# environmental_monitor.net
KiCad netlist of a schematic drawn in EAGLE
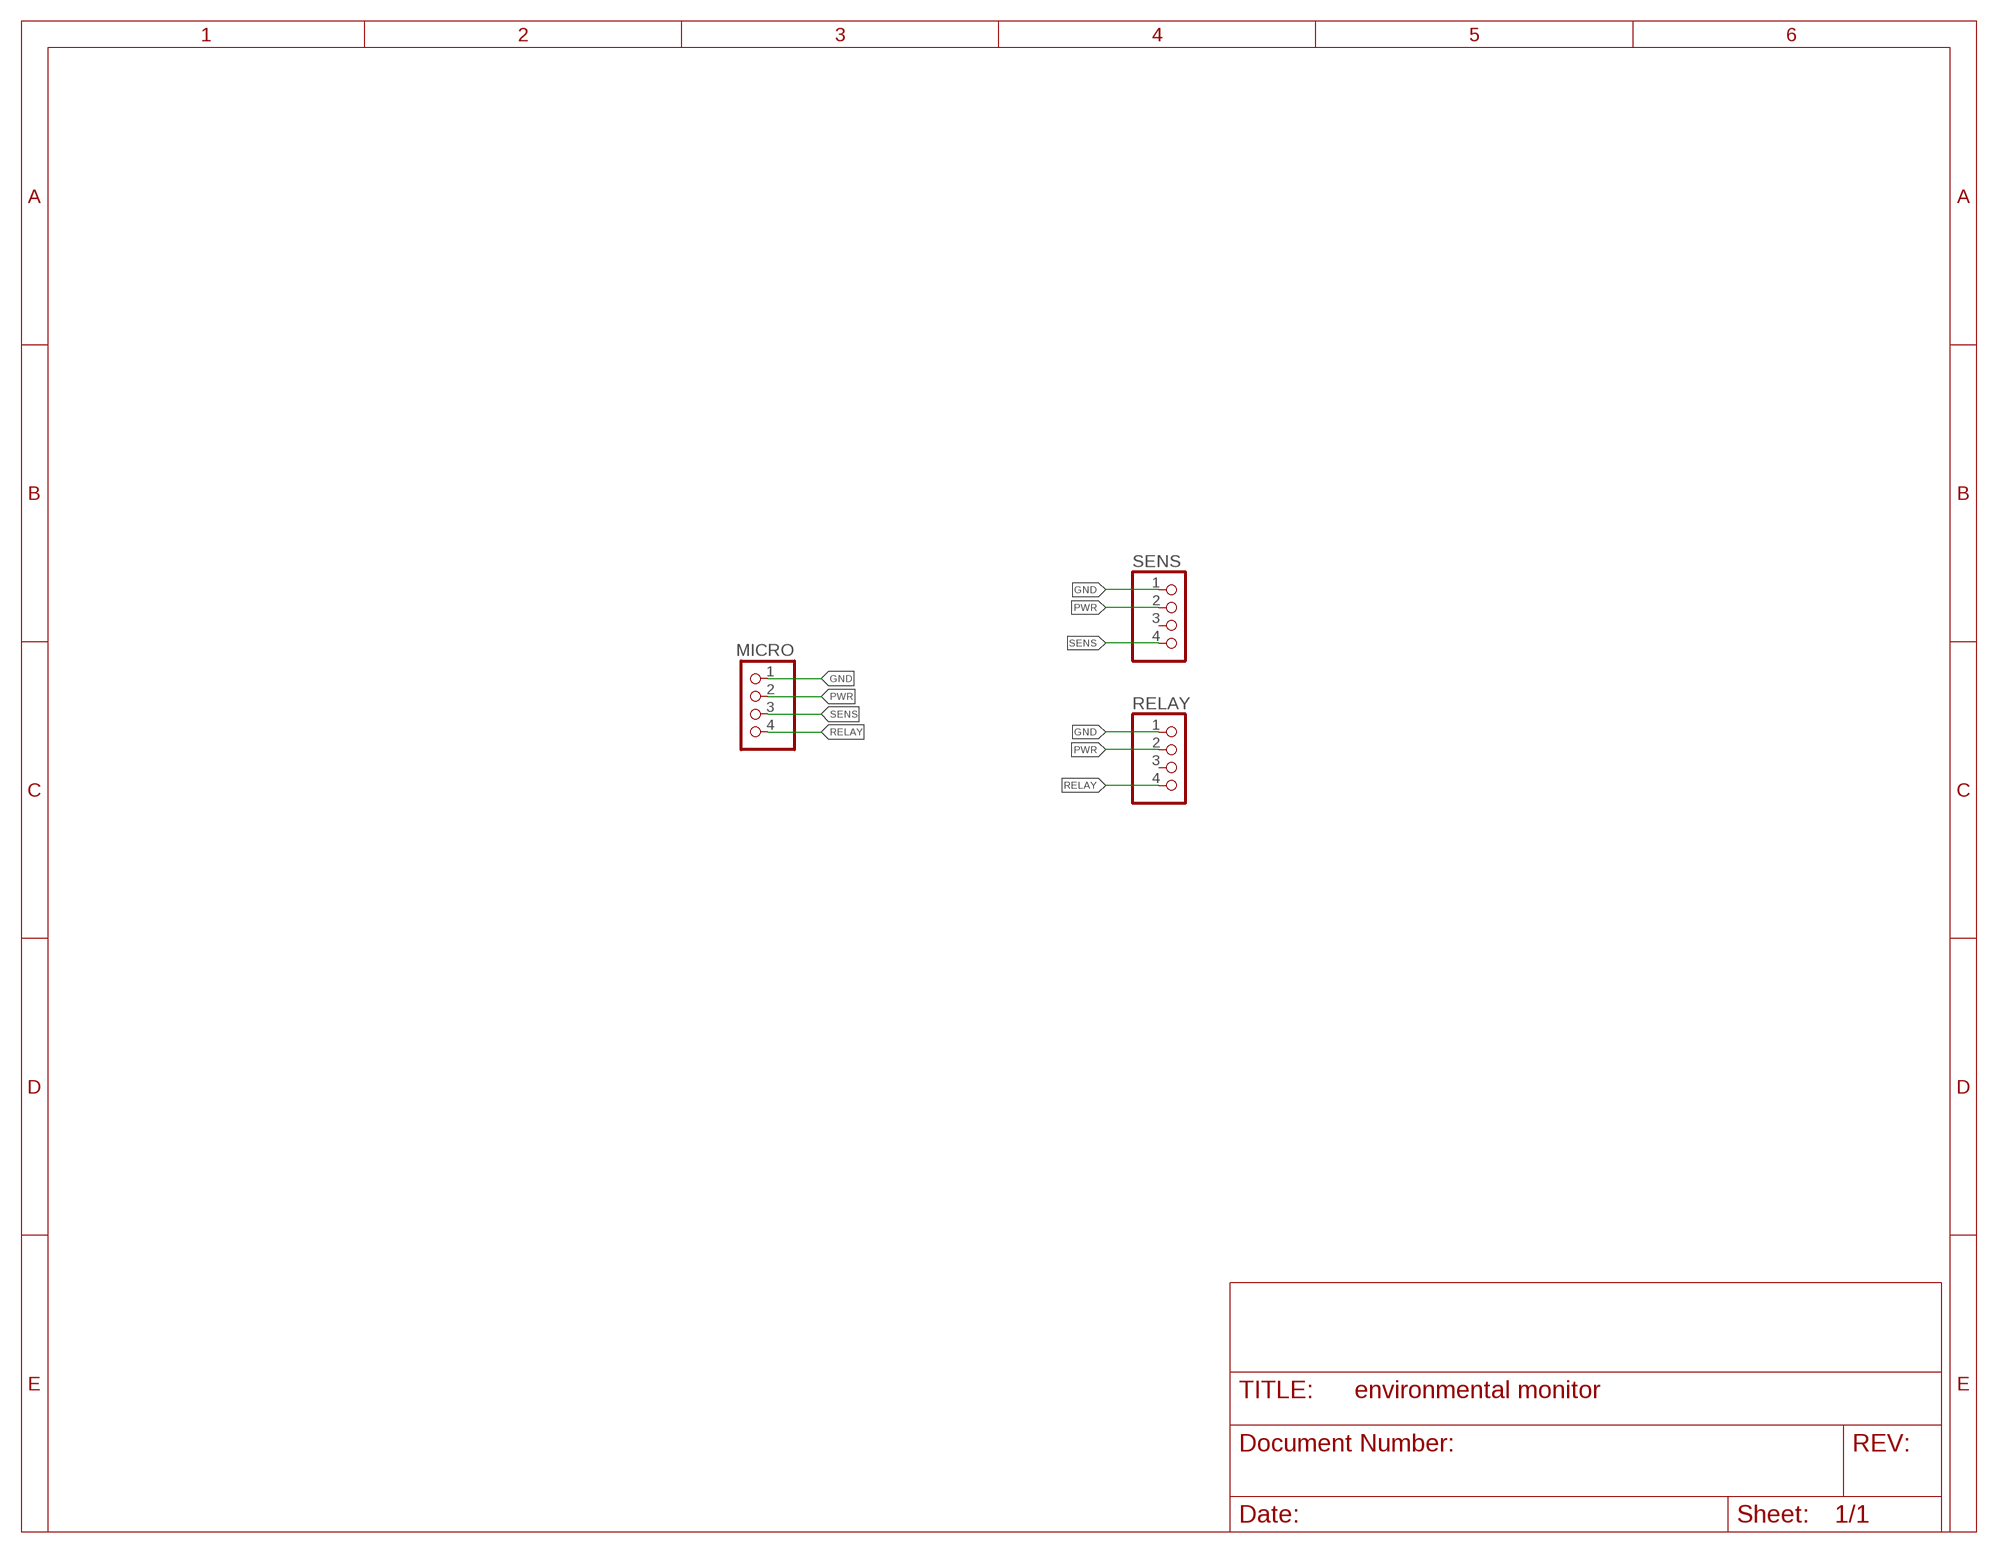
[diagram p0: schematic, sheet 1]

(export (version "E")
  (design (tool "Eeschema 10.0.6"))
  (components
    (comp (ref "MICRO")
      (value "PINHD-1X4")
      (footprint "eagle-import:1X04")
      (libsource (lib "eagle-import") (part "PINHD-1X4"))
    )
    (comp (ref "RELAY")
      (value "PINHD-1X4")
      (footprint "eagle-import:1X04")
      (libsource (lib "eagle-import") (part "PINHD-1X4"))
    )
    (comp (ref "SENS")
      (value "PINHD-1X4")
      (footprint "eagle-import:1X04")
      (libsource (lib "eagle-import") (part "PINHD-1X4"))
    )
  )
  (nets
    (net (code "1") (name "GND") (class "Default")
      (node (ref "MICRO") (pin "1") (pinfunction "1_1") (pintype "passive"))
      (node (ref "RELAY") (pin "1") (pinfunction "1_1") (pintype "passive"))
      (node (ref "SENS") (pin "1") (pinfunction "1_1") (pintype "passive"))
    )
    (net (code "2") (name "PWR") (class "Default")
      (node (ref "MICRO") (pin "2") (pinfunction "2_2") (pintype "passive"))
      (node (ref "RELAY") (pin "2") (pinfunction "2_2") (pintype "passive"))
      (node (ref "SENS") (pin "2") (pinfunction "2_2") (pintype "passive"))
    )
    (net (code "3") (name "RELAY") (class "Default")
      (node (ref "MICRO") (pin "4") (pinfunction "4_4") (pintype "passive"))
      (node (ref "RELAY") (pin "4") (pinfunction "4_4") (pintype "passive"))
    )
    (net (code "4") (name "SENS") (class "Default")
      (node (ref "MICRO") (pin "3") (pinfunction "3_3") (pintype "passive"))
      (node (ref "SENS") (pin "4") (pinfunction "4_4") (pintype "passive"))
    )
    (net (code "5") (name "unconnected-(RELAY-Pad3)") (class "Default")
      (node (ref "RELAY") (pin "3") (pinfunction "3_3") (pintype "passive"))
    )
    (net (code "6") (name "unconnected-(SENS-Pad3)") (class "Default")
      (node (ref "SENS") (pin "3") (pinfunction "3_3") (pintype "passive"))
    )
  )
)
